# UPS.net
KiCad netlist of a schematic drawn in EAGLE
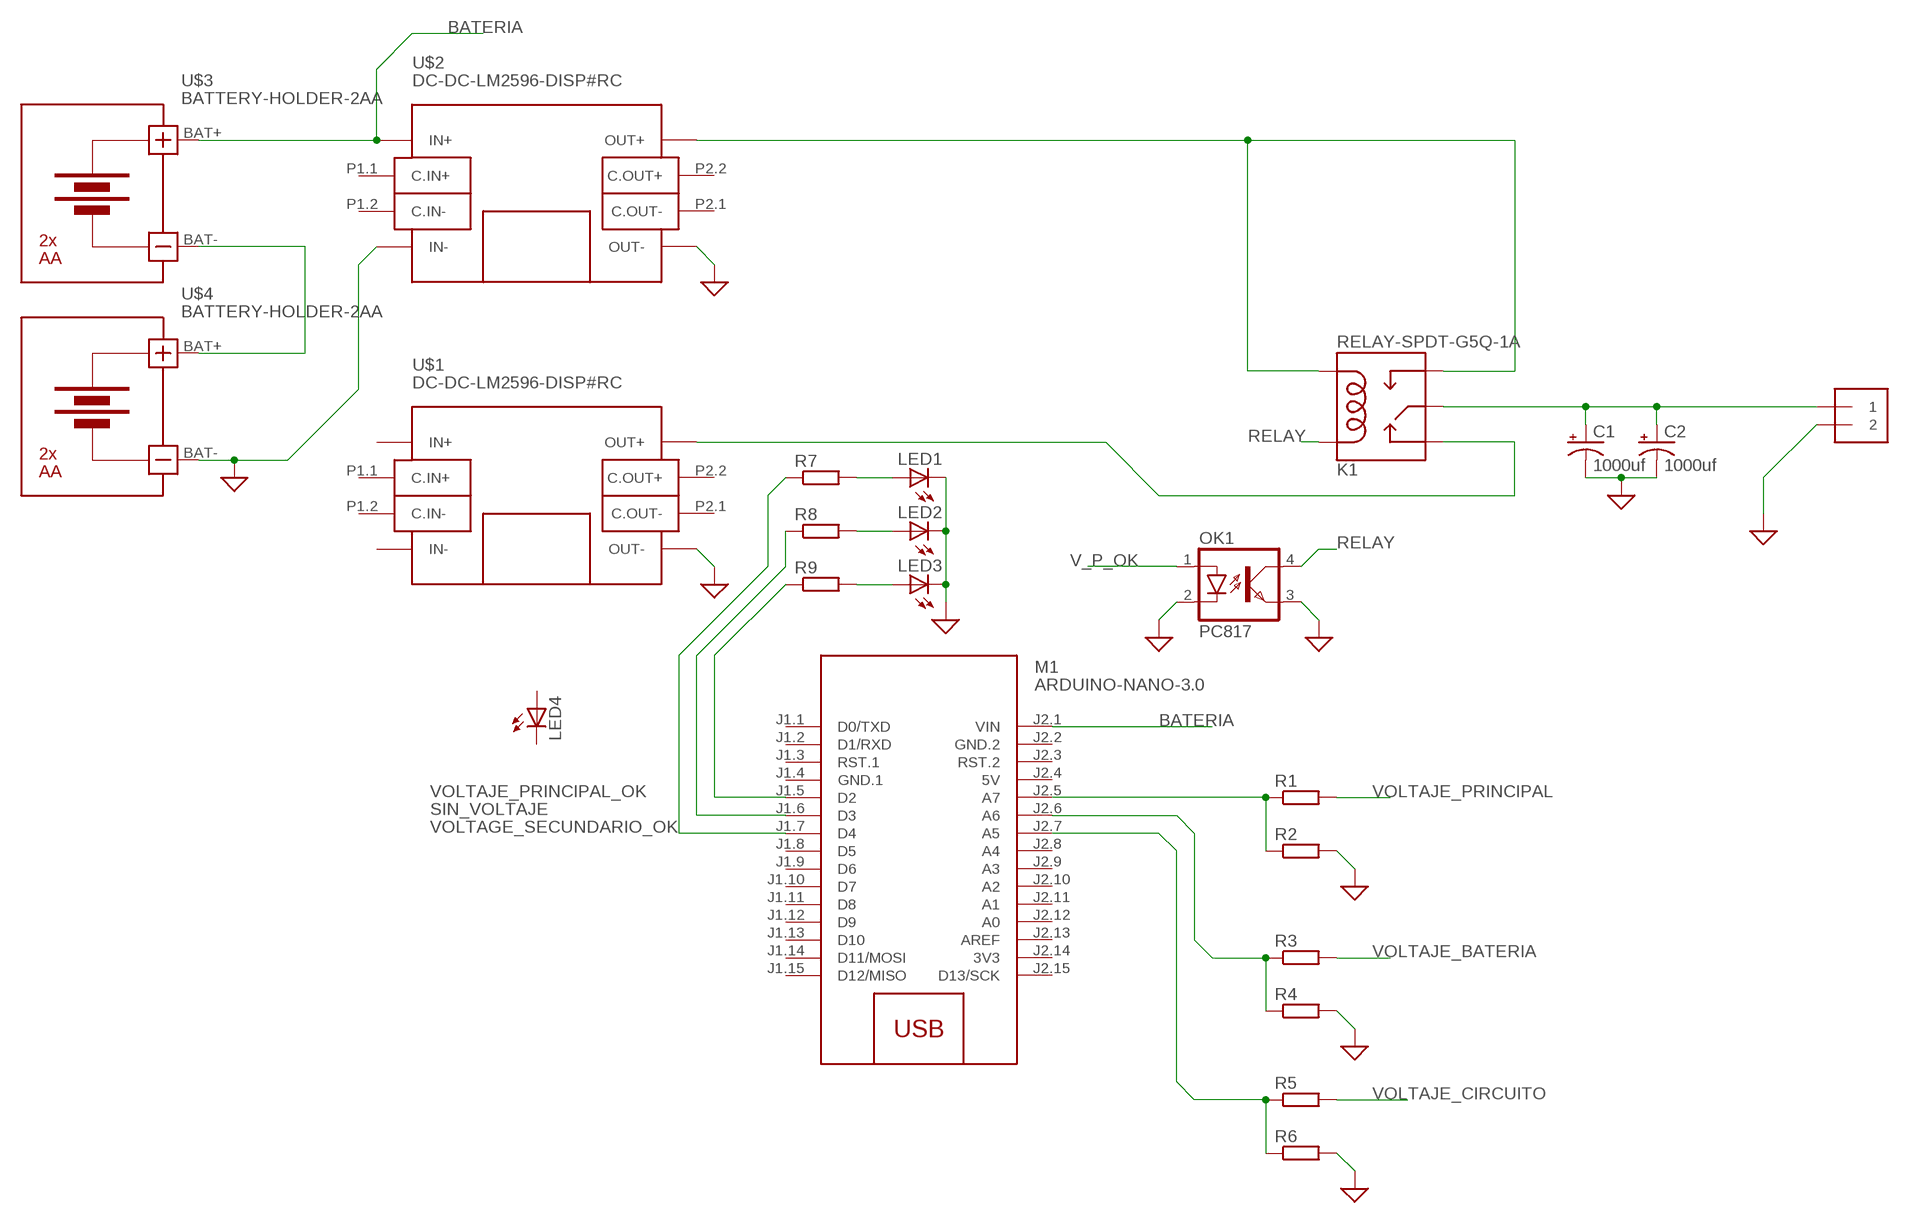
[diagram p0: schematic, sheet 1]

(export (version "E")
  (design (tool "Eeschema 10.0.6"))
  (components
    (comp (ref "C1")
      (value "1000uf")
      (footprint "eagle-import:CPOL-RADIAL-5MM-10MM")
      (libsource (lib "eagle-import") (part "1000UF-RADIAL-5MM-25V-20%"))
    )
    (comp (ref "C2")
      (value "1000uf")
      (footprint "eagle-import:CPOL-RADIAL-5MM-10MM")
      (libsource (lib "eagle-import") (part "1000UF-RADIAL-5MM-25V-20%"))
    )
    (comp (ref "J1")
      (value "1X2-3.5MM")
      (footprint "eagle-import:1X2-3.5MM")
      (libsource (lib "eagle-import") (part "1X2-3.5MM"))
    )
    (comp (ref "K1")
      (value "RELAY-SPDT-G5Q-1A")
      (footprint "eagle-import:RELAY-G5Q")
      (libsource (lib "eagle-import") (part "RELAY-SPDT-G5Q-1A"))
    )
    (comp (ref "LED1")
      (value "LED5MM")
      (footprint "eagle-import:LED5MM")
      (libsource (lib "eagle-import") (part "LED5MM"))
    )
    (comp (ref "LED2")
      (value "LED5MM")
      (footprint "eagle-import:LED5MM")
      (libsource (lib "eagle-import") (part "LED5MM"))
    )
    (comp (ref "LED3")
      (value "LED5MM")
      (footprint "eagle-import:LED5MM")
      (libsource (lib "eagle-import") (part "LED5MM"))
    )
    (comp (ref "LED4")
      (value "LED5MM")
      (footprint "eagle-import:LED5MM")
      (libsource (lib "eagle-import") (part "LED5MM"))
    )
    (comp (ref "M1")
      (value "ARDUINO-NANO-3.0")
      (footprint "eagle-import:ARDUINO-NANO-3.0")
      (libsource (lib "eagle-import") (part "ARDUINO-NANO-3.0"))
    )
    (comp (ref "OK1")
      (value "PC817")
      (footprint "eagle-import:DIL04")
      (fields (field (name "MPN") "PC817X4J000F"))
      (libsource (lib "eagle-import") (part "PC817"))
    )
    (comp (ref "R1")
      (value "R-EU_0207/10")
      (footprint "eagle-import:0207_10")
      (libsource (lib "eagle-import") (part "R-EU_0207/10"))
    )
    (comp (ref "R2")
      (value "R-EU_0207/10")
      (footprint "eagle-import:0207_10")
      (libsource (lib "eagle-import") (part "R-EU_0207/10"))
    )
    (comp (ref "R3")
      (value "R-EU_0207/10")
      (footprint "eagle-import:0207_10")
      (libsource (lib "eagle-import") (part "R-EU_0207/10"))
    )
    (comp (ref "R4")
      (value "R-EU_0207/10")
      (footprint "eagle-import:0207_10")
      (libsource (lib "eagle-import") (part "R-EU_0207/10"))
    )
    (comp (ref "R5")
      (value "R-EU_0207/10")
      (footprint "eagle-import:0207_10")
      (libsource (lib "eagle-import") (part "R-EU_0207/10"))
    )
    (comp (ref "R6")
      (value "R-EU_0207/10")
      (footprint "eagle-import:0207_10")
      (libsource (lib "eagle-import") (part "R-EU_0207/10"))
    )
    (comp (ref "R7")
      (value "R-EU_0207/10")
      (footprint "eagle-import:0207_10")
      (libsource (lib "eagle-import") (part "R-EU_0207/10"))
    )
    (comp (ref "R8")
      (value "R-EU_0207/10")
      (footprint "eagle-import:0207_10")
      (libsource (lib "eagle-import") (part "R-EU_0207/10"))
    )
    (comp (ref "R9")
      (value "R-EU_0207/10")
      (footprint "eagle-import:0207_10")
      (libsource (lib "eagle-import") (part "R-EU_0207/10"))
    )
    (comp (ref "U$1")
      (value "DC-DC-LM2596-DISP#RC")
      (footprint "eagle-import:DC-DC-LM2596-DISP#RC")
      (libsource (lib "eagle-import") (part "DC-DC-LM2596-DISP#RC"))
    )
    (comp (ref "U$2")
      (value "DC-DC-LM2596-DISP#RC")
      (footprint "eagle-import:DC-DC-LM2596-DISP#RC")
      (libsource (lib "eagle-import") (part "DC-DC-LM2596-DISP#RC"))
    )
    (comp (ref "U$3")
      (value "BATTERY-HOLDER-2AA")
      (footprint "eagle-import:BATTERY-HOLDER-2AA")
      (libsource (lib "eagle-import") (part "BATTERY-HOLDER-2AA"))
    )
    (comp (ref "U$4")
      (value "BATTERY-HOLDER-2AA")
      (footprint "eagle-import:BATTERY-HOLDER-2AA")
      (libsource (lib "eagle-import") (part "BATTERY-HOLDER-2AA"))
    )
  )
  (nets
    (net (code "1") (name "/3V3") (class "Default")
      (node (ref "M1") (pin "J2.14") (pinfunction "3V3_J2.14") (pintype "power_in"))
    )
    (net (code "2") (name "/5V") (class "Default")
      (node (ref "M1") (pin "J2.4") (pinfunction "5V_J2.4") (pintype "power_in"))
    )
    (net (code "3") (name "/BATERIA") (class "Default")
      (node (ref "M1") (pin "J2.1") (pinfunction "VIN_J2.1") (pintype "power_in"))
      (node (ref "U$2") (pin "IN+") (pinfunction "IN+_IN+") (pintype "bidirectional"))
      (node (ref "U$3") (pin "BAT+") (pinfunction "BAT+_BAT+") (pintype "power_in"))
    )
    (net (code "4") (name "/GND.1") (class "Default")
      (node (ref "M1") (pin "J1.4") (pinfunction "GND.1_J1.4") (pintype "power_in"))
    )
    (net (code "5") (name "/GND.2") (class "Default")
      (node (ref "M1") (pin "J2.2") (pinfunction "GND.2_J2.2") (pintype "power_in"))
    )
    (net (code "6") (name "/RELAY") (class "Default")
      (node (ref "K1") (pin "5") (pinfunction "COIL1_5") (pintype "bidirectional"))
      (node (ref "OK1") (pin "4") (pinfunction "COL_4") (pintype "passive"))
    )
    (net (code "7") (name "/SIN_VOLTAJE") (class "Default")
      (node (ref "M1") (pin "J1.6") (pinfunction "D3_J1.6") (pintype "bidirectional"))
      (node (ref "R8") (pin "1") (pinfunction "1_1") (pintype "passive"))
    )
    (net (code "8") (name "/VOLTAGE_SECUNDARIO_OK") (class "Default")
      (node (ref "M1") (pin "J1.7") (pinfunction "D4_J1.7") (pintype "bidirectional"))
      (node (ref "R7") (pin "1") (pinfunction "1_1") (pintype "passive"))
    )
    (net (code "9") (name "/VOLTAJE_BATERIA") (class "Default")
      (node (ref "R3") (pin "2") (pinfunction "2_2") (pintype "passive"))
    )
    (net (code "10") (name "/VOLTAJE_CIRCUITO") (class "Default")
      (node (ref "R5") (pin "2") (pinfunction "2_2") (pintype "passive"))
    )
    (net (code "11") (name "/VOLTAJE_PRINCIPAL") (class "Default")
      (node (ref "R1") (pin "2") (pinfunction "2_2") (pintype "passive"))
    )
    (net (code "12") (name "/VOLTAJE_PRINCIPAL_OK") (class "Default")
      (node (ref "M1") (pin "J1.5") (pinfunction "D2_J1.5") (pintype "bidirectional"))
      (node (ref "R9") (pin "1") (pinfunction "1_1") (pintype "passive"))
    )
    (net (code "13") (name "/V_P_OK") (class "Default")
      (node (ref "OK1") (pin "1") (pinfunction "A_1") (pintype "passive"))
    )
    (net (code "14") (name "Net-(K1-COIL2)") (class "Default")
      (node (ref "K1") (pin "1") (pinfunction "COIL2_1") (pintype "bidirectional"))
      (node (ref "K1") (pin "3") (pinfunction "NO_3") (pintype "bidirectional"))
      (node (ref "U$2") (pin "OUT+") (pinfunction "OUT+_OUT+") (pintype "bidirectional"))
    )
    (net (code "15") (name "Net-(K1-MAIN)") (class "Default")
      (node (ref "C1") (pin "+") (pinfunction "+_+") (pintype "passive"))
      (node (ref "C2") (pin "+") (pinfunction "+_+") (pintype "passive"))
      (node (ref "J1") (pin "1") (pinfunction "1_1") (pintype "passive"))
      (node (ref "K1") (pin "2") (pinfunction "MAIN_2") (pintype "bidirectional"))
    )
    (net (code "16") (name "Net-(K1-NC)") (class "Default")
      (node (ref "K1") (pin "4") (pinfunction "NC_4") (pintype "bidirectional"))
      (node (ref "U$1") (pin "OUT+") (pinfunction "OUT+_OUT+") (pintype "bidirectional"))
    )
    (net (code "17") (name "Net-(LED1-PadA)") (class "Default")
      (node (ref "LED1") (pin "A") (pinfunction "A_A") (pintype "passive"))
      (node (ref "R7") (pin "2") (pinfunction "2_2") (pintype "passive"))
    )
    (net (code "18") (name "Net-(LED2-PadA)") (class "Default")
      (node (ref "LED2") (pin "A") (pinfunction "A_A") (pintype "passive"))
      (node (ref "R8") (pin "2") (pinfunction "2_2") (pintype "passive"))
    )
    (net (code "19") (name "Net-(LED3-PadA)") (class "Default")
      (node (ref "LED3") (pin "A") (pinfunction "A_A") (pintype "passive"))
      (node (ref "R9") (pin "2") (pinfunction "2_2") (pintype "passive"))
    )
    (net (code "20") (name "Net-(M1-A5)") (class "Default")
      (node (ref "M1") (pin "J2.7") (pinfunction "A5_J2.7") (pintype "bidirectional"))
      (node (ref "R5") (pin "1") (pinfunction "1_1") (pintype "passive"))
      (node (ref "R6") (pin "1") (pinfunction "1_1") (pintype "passive"))
    )
    (net (code "21") (name "Net-(M1-A6)") (class "Default")
      (node (ref "M1") (pin "J2.6") (pinfunction "A6_J2.6") (pintype "bidirectional"))
      (node (ref "R3") (pin "1") (pinfunction "1_1") (pintype "passive"))
      (node (ref "R4") (pin "1") (pinfunction "1_1") (pintype "passive"))
    )
    (net (code "22") (name "Net-(M1-A7)") (class "Default")
      (node (ref "M1") (pin "J2.5") (pinfunction "A7_J2.5") (pintype "bidirectional"))
      (node (ref "R1") (pin "1") (pinfunction "1_1") (pintype "passive"))
      (node (ref "R2") (pin "1") (pinfunction "1_1") (pintype "passive"))
    )
    (net (code "23") (name "Net-(U$3-PadBAT-)") (class "Default")
      (node (ref "U$3") (pin "BAT-") (pinfunction "BAT-_BAT-") (pintype "power_in"))
      (node (ref "U$4") (pin "BAT+") (pinfunction "BAT+_BAT+") (pintype "power_in"))
    )
    (net (code "24") (name "SUP") (class "Default")
      (node (ref "C1") (pin "-") (pinfunction "-_-") (pintype "passive"))
      (node (ref "C2") (pin "-") (pinfunction "-_-") (pintype "passive"))
      (node (ref "J1") (pin "2") (pinfunction "2_2") (pintype "passive"))
      (node (ref "LED1") (pin "K") (pinfunction "C_K") (pintype "passive"))
      (node (ref "LED2") (pin "K") (pinfunction "C_K") (pintype "passive"))
      (node (ref "LED3") (pin "K") (pinfunction "C_K") (pintype "passive"))
      (node (ref "OK1") (pin "2") (pinfunction "C_2") (pintype "passive"))
      (node (ref "OK1") (pin "3") (pinfunction "EMIT_3") (pintype "passive"))
      (node (ref "R2") (pin "2") (pinfunction "2_2") (pintype "passive"))
      (node (ref "R4") (pin "2") (pinfunction "2_2") (pintype "passive"))
      (node (ref "R6") (pin "2") (pinfunction "2_2") (pintype "passive"))
      (node (ref "U$1") (pin "OUT-") (pinfunction "OUT-_OUT-") (pintype "bidirectional"))
      (node (ref "U$2") (pin "IN-") (pinfunction "IN-_IN-") (pintype "bidirectional"))
      (node (ref "U$2") (pin "OUT-") (pinfunction "OUT-_OUT-") (pintype "bidirectional"))
      (node (ref "U$4") (pin "BAT-") (pinfunction "BAT-_BAT-") (pintype "power_in"))
    )
    (net (code "25") (name "unconnected-(LED4-C-PadK)") (class "Default")
      (node (ref "LED4") (pin "K") (pinfunction "C_K") (pintype "passive"))
    )
    (net (code "26") (name "unconnected-(LED4-PadA)") (class "Default")
      (node (ref "LED4") (pin "A") (pinfunction "A_A") (pintype "passive"))
    )
    (net (code "27") (name "unconnected-(M1-A0-PadJ2.12)") (class "Default")
      (node (ref "M1") (pin "J2.12") (pinfunction "A0_J2.12") (pintype "bidirectional"))
    )
    (net (code "28") (name "unconnected-(M1-A1-PadJ2.11)") (class "Default")
      (node (ref "M1") (pin "J2.11") (pinfunction "A1_J2.11") (pintype "bidirectional"))
    )
    (net (code "29") (name "unconnected-(M1-A2-PadJ2.10)") (class "Default")
      (node (ref "M1") (pin "J2.10") (pinfunction "A2_J2.10") (pintype "bidirectional"))
    )
    (net (code "30") (name "unconnected-(M1-A3-PadJ2.9)") (class "Default")
      (node (ref "M1") (pin "J2.9") (pinfunction "A3_J2.9") (pintype "bidirectional"))
    )
    (net (code "31") (name "unconnected-(M1-A4-PadJ2.8)") (class "Default")
      (node (ref "M1") (pin "J2.8") (pinfunction "A4_J2.8") (pintype "bidirectional"))
    )
    (net (code "32") (name "unconnected-(M1-AREF-PadJ2.13)") (class "Default")
      (node (ref "M1") (pin "J2.13") (pinfunction "AREF_J2.13") (pintype "bidirectional"))
    )
    (net (code "33") (name "unconnected-(M1-D0{slash}TXD-PadJ1.1)") (class "Default")
      (node (ref "M1") (pin "J1.1") (pinfunction "D0/TXD_J1.1") (pintype "bidirectional"))
    )
    (net (code "34") (name "unconnected-(M1-D1{slash}RXD-PadJ1.2)") (class "Default")
      (node (ref "M1") (pin "J1.2") (pinfunction "D1/RXD_J1.2") (pintype "bidirectional"))
    )
    (net (code "35") (name "unconnected-(M1-D5-PadJ1.8)") (class "Default")
      (node (ref "M1") (pin "J1.8") (pinfunction "D5_J1.8") (pintype "bidirectional"))
    )
    (net (code "36") (name "unconnected-(M1-D6-PadJ1.9)") (class "Default")
      (node (ref "M1") (pin "J1.9") (pinfunction "D6_J1.9") (pintype "bidirectional"))
    )
    (net (code "37") (name "unconnected-(M1-D7-PadJ1.10)") (class "Default")
      (node (ref "M1") (pin "J1.10") (pinfunction "D7_J1.10") (pintype "bidirectional"))
    )
    (net (code "38") (name "unconnected-(M1-D8-PadJ1.11)") (class "Default")
      (node (ref "M1") (pin "J1.11") (pinfunction "D8_J1.11") (pintype "bidirectional"))
    )
    (net (code "39") (name "unconnected-(M1-D9-PadJ1.12)") (class "Default")
      (node (ref "M1") (pin "J1.12") (pinfunction "D9_J1.12") (pintype "bidirectional"))
    )
    (net (code "40") (name "unconnected-(M1-D10-PadJ1.13)") (class "Default")
      (node (ref "M1") (pin "J1.13") (pinfunction "D10_J1.13") (pintype "bidirectional"))
    )
    (net (code "41") (name "unconnected-(M1-D11{slash}MOSI-PadJ1.14)") (class "Default")
      (node (ref "M1") (pin "J1.14") (pinfunction "D11/MOSI_J1.14") (pintype "bidirectional"))
    )
    (net (code "42") (name "unconnected-(M1-D12{slash}MISO-PadJ1.15)") (class "Default")
      (node (ref "M1") (pin "J1.15") (pinfunction "D12/MISO_J1.15") (pintype "bidirectional"))
    )
    (net (code "43") (name "unconnected-(M1-D13{slash}SCK-PadJ2.15)") (class "Default")
      (node (ref "M1") (pin "J2.15") (pinfunction "D13/SCK_J2.15") (pintype "bidirectional"))
    )
    (net (code "44") (name "unconnected-(M1-RST.1-PadJ1.3)") (class "Default")
      (node (ref "M1") (pin "J1.3") (pinfunction "RST.1_J1.3") (pintype "bidirectional"))
    )
    (net (code "45") (name "unconnected-(M1-RST.2-PadJ2.3)") (class "Default")
      (node (ref "M1") (pin "J2.3") (pinfunction "RST.2_J2.3") (pintype "bidirectional"))
    )
    (net (code "46") (name "unconnected-(U$1-C.IN+-PadP1.1)") (class "Default")
      (node (ref "U$1") (pin "P1.1") (pinfunction "C.IN+_P1.1") (pintype "bidirectional"))
    )
    (net (code "47") (name "unconnected-(U$1-C.IN--PadP1.2)") (class "Default")
      (node (ref "U$1") (pin "P1.2") (pinfunction "C.IN-_P1.2") (pintype "bidirectional"))
    )
    (net (code "48") (name "unconnected-(U$1-C.OUT+-PadP2.2)") (class "Default")
      (node (ref "U$1") (pin "P2.2") (pinfunction "C.OUT+_P2.2") (pintype "bidirectional"))
    )
    (net (code "49") (name "unconnected-(U$1-C.OUT--PadP2.1)") (class "Default")
      (node (ref "U$1") (pin "P2.1") (pinfunction "C.OUT-_P2.1") (pintype "bidirectional"))
    )
    (net (code "50") (name "unconnected-(U$1-PadIN+)") (class "Default")
      (node (ref "U$1") (pin "IN+") (pinfunction "IN+_IN+") (pintype "bidirectional"))
    )
    (net (code "51") (name "unconnected-(U$1-PadIN-)") (class "Default")
      (node (ref "U$1") (pin "IN-") (pinfunction "IN-_IN-") (pintype "bidirectional"))
    )
    (net (code "52") (name "unconnected-(U$2-C.IN+-PadP1.1)") (class "Default")
      (node (ref "U$2") (pin "P1.1") (pinfunction "C.IN+_P1.1") (pintype "bidirectional"))
    )
    (net (code "53") (name "unconnected-(U$2-C.IN--PadP1.2)") (class "Default")
      (node (ref "U$2") (pin "P1.2") (pinfunction "C.IN-_P1.2") (pintype "bidirectional"))
    )
    (net (code "54") (name "unconnected-(U$2-C.OUT+-PadP2.2)") (class "Default")
      (node (ref "U$2") (pin "P2.2") (pinfunction "C.OUT+_P2.2") (pintype "bidirectional"))
    )
    (net (code "55") (name "unconnected-(U$2-C.OUT--PadP2.1)") (class "Default")
      (node (ref "U$2") (pin "P2.1") (pinfunction "C.OUT-_P2.1") (pintype "bidirectional"))
    )
  )
)
